# Relay_Board_Schematic.net
KiCad netlist of a schematic drawn in Altium Designer
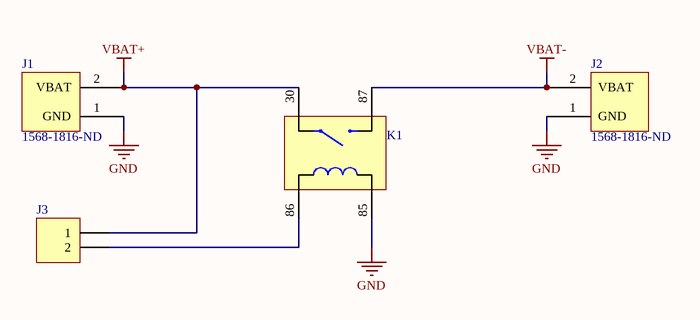
[diagram p0: Relay Board Schematic.SchDoc]

(export (version "E")
  (design (tool "Eeschema 10.0.6"))
  (components
    (comp (ref "J1")
      (value "CONN_XT60")
      (footprint "XT60_CONN")
      (description "XT60 Connectors Male/female Pair")
      (fields
        (field (name "MANUFACTURER") "SparkFun")
        (field (name "MANUFACTURER PART NUMBER") "PRT-10474")
        (field (name "SUPPLIER PART NUMBER 1") "1568-1816-ND")
      )
      (libsource (lib "Main Schematic Library") (part "CONN_XT60"))
    )
    (comp (ref "J2")
      (value "CONN_XT60")
      (footprint "XT60_CONN")
      (description "XT60 Connectors Male/female Pair")
      (fields
        (field (name "MANUFACTURER") "SparkFun")
        (field (name "MANUFACTURER PART NUMBER") "PRT-10474")
        (field (name "SUPPLIER PART NUMBER 1") "1568-1816-ND")
      )
      (libsource (lib "") (part "CONN_XT60_1"))
    )
    (comp (ref "J3")
      (value "CONN_HDR_1X2")
      (footprint "HDR1X2")
      (description "Header, 2-Pin")
      (fields (field (name "PUBLISHER") "Altium Limited"))
      (libsource (lib "Main Component Library") (part "CONN_HDR_1X2"))
    )
    (comp (ref "K1")
      (value "RLY_ELO_MINI_POWER_RELAY_24V_70A")
      (footprint "ELO_MINI_POWER_RELAY")
      (libsource (lib "Main Component Library") (part "RLY_ELO_MINI_POWER_RELAY_24V_70A"))
    )
  )
  (nets
    (net (code "1") (name "GND") (class "Default")
      (node (ref "J1") (pin "1") (pinfunction "GND_1") (pintype "passive"))
      (node (ref "J2") (pin "1") (pinfunction "GND_1") (pintype "passive"))
      (node (ref "K1") (pin "85") (pinfunction "2_85") (pintype "passive"))
    )
    (net (code "2") (name "Net-(K1-1)") (class "Default")
      (node (ref "J3") (pin "2") (pinfunction "2_2") (pintype "passive"))
      (node (ref "K1") (pin "86") (pinfunction "1_86") (pintype "passive"))
    )
    (net (code "3") (name "VBAT+") (class "Default")
      (node (ref "J1") (pin "2") (pinfunction "VBAT_2") (pintype "passive"))
      (node (ref "J3") (pin "1") (pinfunction "1_1") (pintype "passive"))
      (node (ref "K1") (pin "30") (pinfunction "3_30") (pintype "passive"))
    )
    (net (code "4") (name "VBAT-") (class "Default")
      (node (ref "J2") (pin "2") (pinfunction "VBAT_2") (pintype "passive"))
      (node (ref "K1") (pin "87") (pinfunction "4_87") (pintype "passive"))
    )
  )
)
